# MainSensor.net
KiCad netlist of a schematic drawn in EAGLE
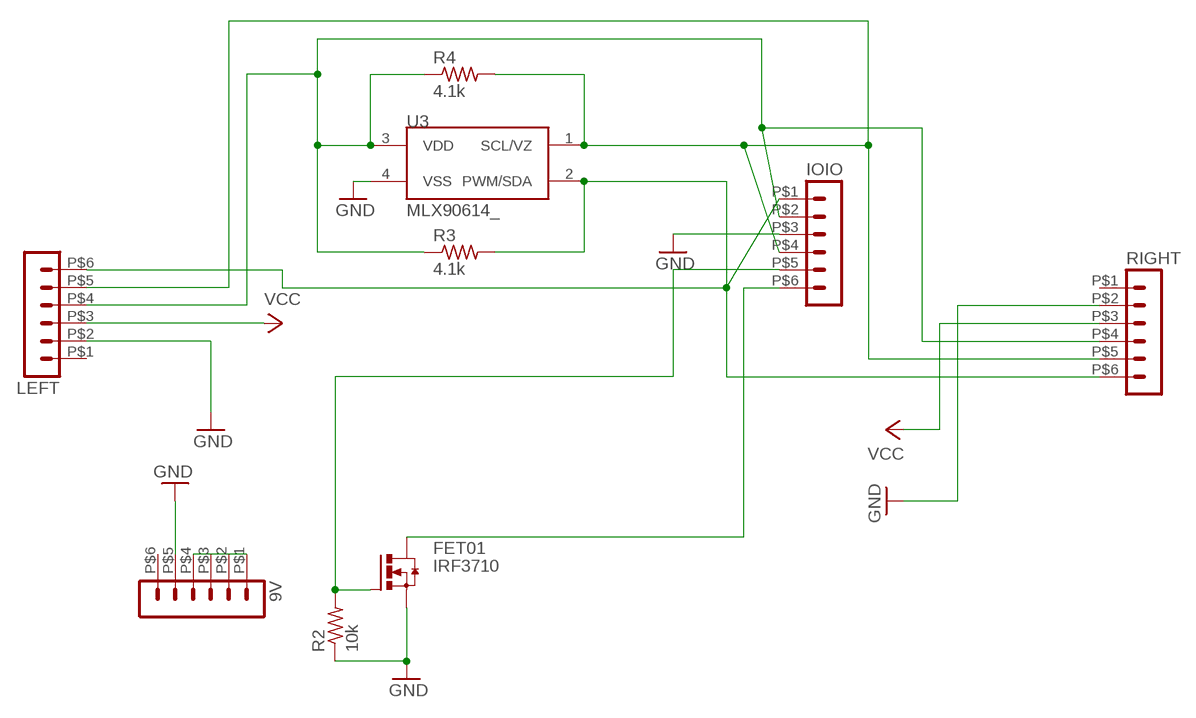
[diagram p0: schematic, sheet 1]

(export (version "E")
  (design (tool "Eeschema 10.0.6"))
  (components
    (comp (ref "9V")
      (value "HEADER_POS6_43045-0600")
      (footprint "eagle-import:43045-0600")
      (libsource (lib "eagle-import") (part "HEADER_POS6_?43045-0600"))
    )
    (comp (ref "FET01")
      (value "IRF3710")
      (footprint "eagle-import:TO220AH")
      (libsource (lib "eagle-import") (part "IRF3704"))
    )
    (comp (ref "IOIO")
      (value "HEADER_POS6_43045-0600")
      (footprint "eagle-import:43045-0600")
      (libsource (lib "eagle-import") (part "HEADER_POS6_?43045-0600"))
    )
    (comp (ref "LEFT")
      (value "HEADER_POS6_43045-0600")
      (footprint "eagle-import:43045-0600")
      (libsource (lib "eagle-import") (part "HEADER_POS6_?43045-0600"))
    )
    (comp (ref "R2")
      (value "10k")
      (footprint "eagle-import:0207_7")
      (libsource (lib "eagle-import") (part "R-US_0207/7"))
    )
    (comp (ref "R3")
      (value "4.1k")
      (footprint "eagle-import:0204_5")
      (libsource (lib "eagle-import") (part "R-US_0204/5"))
    )
    (comp (ref "R4")
      (value "4.1k")
      (footprint "eagle-import:0204_5")
      (libsource (lib "eagle-import") (part "R-US_0204/5"))
    )
    (comp (ref "RIGHT")
      (value "HEADER_POS6_43045-0600")
      (footprint "eagle-import:43045-0600")
      (libsource (lib "eagle-import") (part "HEADER_POS6_?43045-0600"))
    )
    (comp (ref "U3")
      (value "MLX90614_")
      (footprint "eagle-import:TO-39")
      (libsource (lib "eagle-import") (part "MLX90614_"))
    )
  )
  (nets
    (net (code "1") (name "GND") (class "Default")
      (node (ref "9V") (pin "P$5") (pinfunction "5_P$5") (pintype "passive"))
      (node (ref "FET01") (pin "E") (pinfunction "S_E") (pintype "passive"))
      (node (ref "IOIO") (pin "P$3") (pinfunction "3_P$3") (pintype "passive"))
      (node (ref "LEFT") (pin "P$2") (pinfunction "2_P$2") (pintype "passive"))
      (node (ref "R2") (pin "1") (pinfunction "1_1") (pintype "passive"))
      (node (ref "RIGHT") (pin "P$2") (pinfunction "2_P$2") (pintype "passive"))
      (node (ref "U3") (pin "4") (pinfunction "VSS_4") (pintype "bidirectional"))
    )
    (net (code "2") (name "Net-(9V-1)") (class "Default")
      (node (ref "9V") (pin "P$1") (pinfunction "1_P$1") (pintype "passive"))
      (node (ref "9V") (pin "P$2") (pinfunction "2_P$2") (pintype "passive"))
      (node (ref "9V") (pin "P$3") (pinfunction "3_P$3") (pintype "passive"))
      (node (ref "9V") (pin "P$4") (pinfunction "4_P$4") (pintype "passive"))
    )
    (net (code "3") (name "Net-(FET01-D)") (class "Default")
      (node (ref "FET01") (pin "C") (pinfunction "D_C") (pintype "passive"))
      (node (ref "IOIO") (pin "P$6") (pinfunction "6_P$6") (pintype "passive"))
    )
    (net (code "4") (name "Net-(FET01-G)") (class "Default")
      (node (ref "FET01") (pin "B") (pinfunction "G_B") (pintype "passive"))
      (node (ref "IOIO") (pin "P$5") (pinfunction "5_P$5") (pintype "passive"))
      (node (ref "R2") (pin "2") (pinfunction "2_2") (pintype "passive"))
    )
    (net (code "5") (name "Net-(IOIO-1)") (class "Default")
      (node (ref "IOIO") (pin "P$1") (pinfunction "1_P$1") (pintype "passive"))
      (node (ref "LEFT") (pin "P$6") (pinfunction "6_P$6") (pintype "passive"))
      (node (ref "R3") (pin "2") (pinfunction "2_2") (pintype "passive"))
      (node (ref "RIGHT") (pin "P$6") (pinfunction "6_P$6") (pintype "passive"))
      (node (ref "U3") (pin "2") (pinfunction "PWM/SDA_2") (pintype "bidirectional"))
    )
    (net (code "6") (name "Net-(IOIO-2)") (class "Default")
      (node (ref "IOIO") (pin "P$2") (pinfunction "2_P$2") (pintype "passive"))
      (node (ref "LEFT") (pin "P$4") (pinfunction "4_P$4") (pintype "passive"))
      (node (ref "R3") (pin "1") (pinfunction "1_1") (pintype "passive"))
      (node (ref "R4") (pin "1") (pinfunction "1_1") (pintype "passive"))
      (node (ref "RIGHT") (pin "P$4") (pinfunction "4_P$4") (pintype "passive"))
      (node (ref "U3") (pin "3") (pinfunction "VDD_3") (pintype "bidirectional"))
    )
    (net (code "7") (name "Net-(IOIO-4)") (class "Default")
      (node (ref "IOIO") (pin "P$4") (pinfunction "4_P$4") (pintype "passive"))
      (node (ref "LEFT") (pin "P$5") (pinfunction "5_P$5") (pintype "passive"))
      (node (ref "R4") (pin "2") (pinfunction "2_2") (pintype "passive"))
      (node (ref "RIGHT") (pin "P$5") (pinfunction "5_P$5") (pintype "passive"))
      (node (ref "U3") (pin "1") (pinfunction "SCL/VZ_1") (pintype "bidirectional"))
    )
    (net (code "8") (name "VCC") (class "Default")
      (node (ref "LEFT") (pin "P$3") (pinfunction "3_P$3") (pintype "passive"))
      (node (ref "RIGHT") (pin "P$3") (pinfunction "3_P$3") (pintype "passive"))
    )
    (net (code "9") (name "unconnected-(9V-6-PadP$6)") (class "Default")
      (node (ref "9V") (pin "P$6") (pinfunction "6_P$6") (pintype "passive"))
    )
    (net (code "10") (name "unconnected-(LEFT-1-PadP$1)") (class "Default")
      (node (ref "LEFT") (pin "P$1") (pinfunction "1_P$1") (pintype "passive"))
    )
    (net (code "11") (name "unconnected-(RIGHT-1-PadP$1)") (class "Default")
      (node (ref "RIGHT") (pin "P$1") (pinfunction "1_P$1") (pintype "passive"))
    )
  )
)
